# interface_dac_sma_feedback_3PS_LM317_ADC.net
KiCad netlist of a schematic drawn in EAGLE
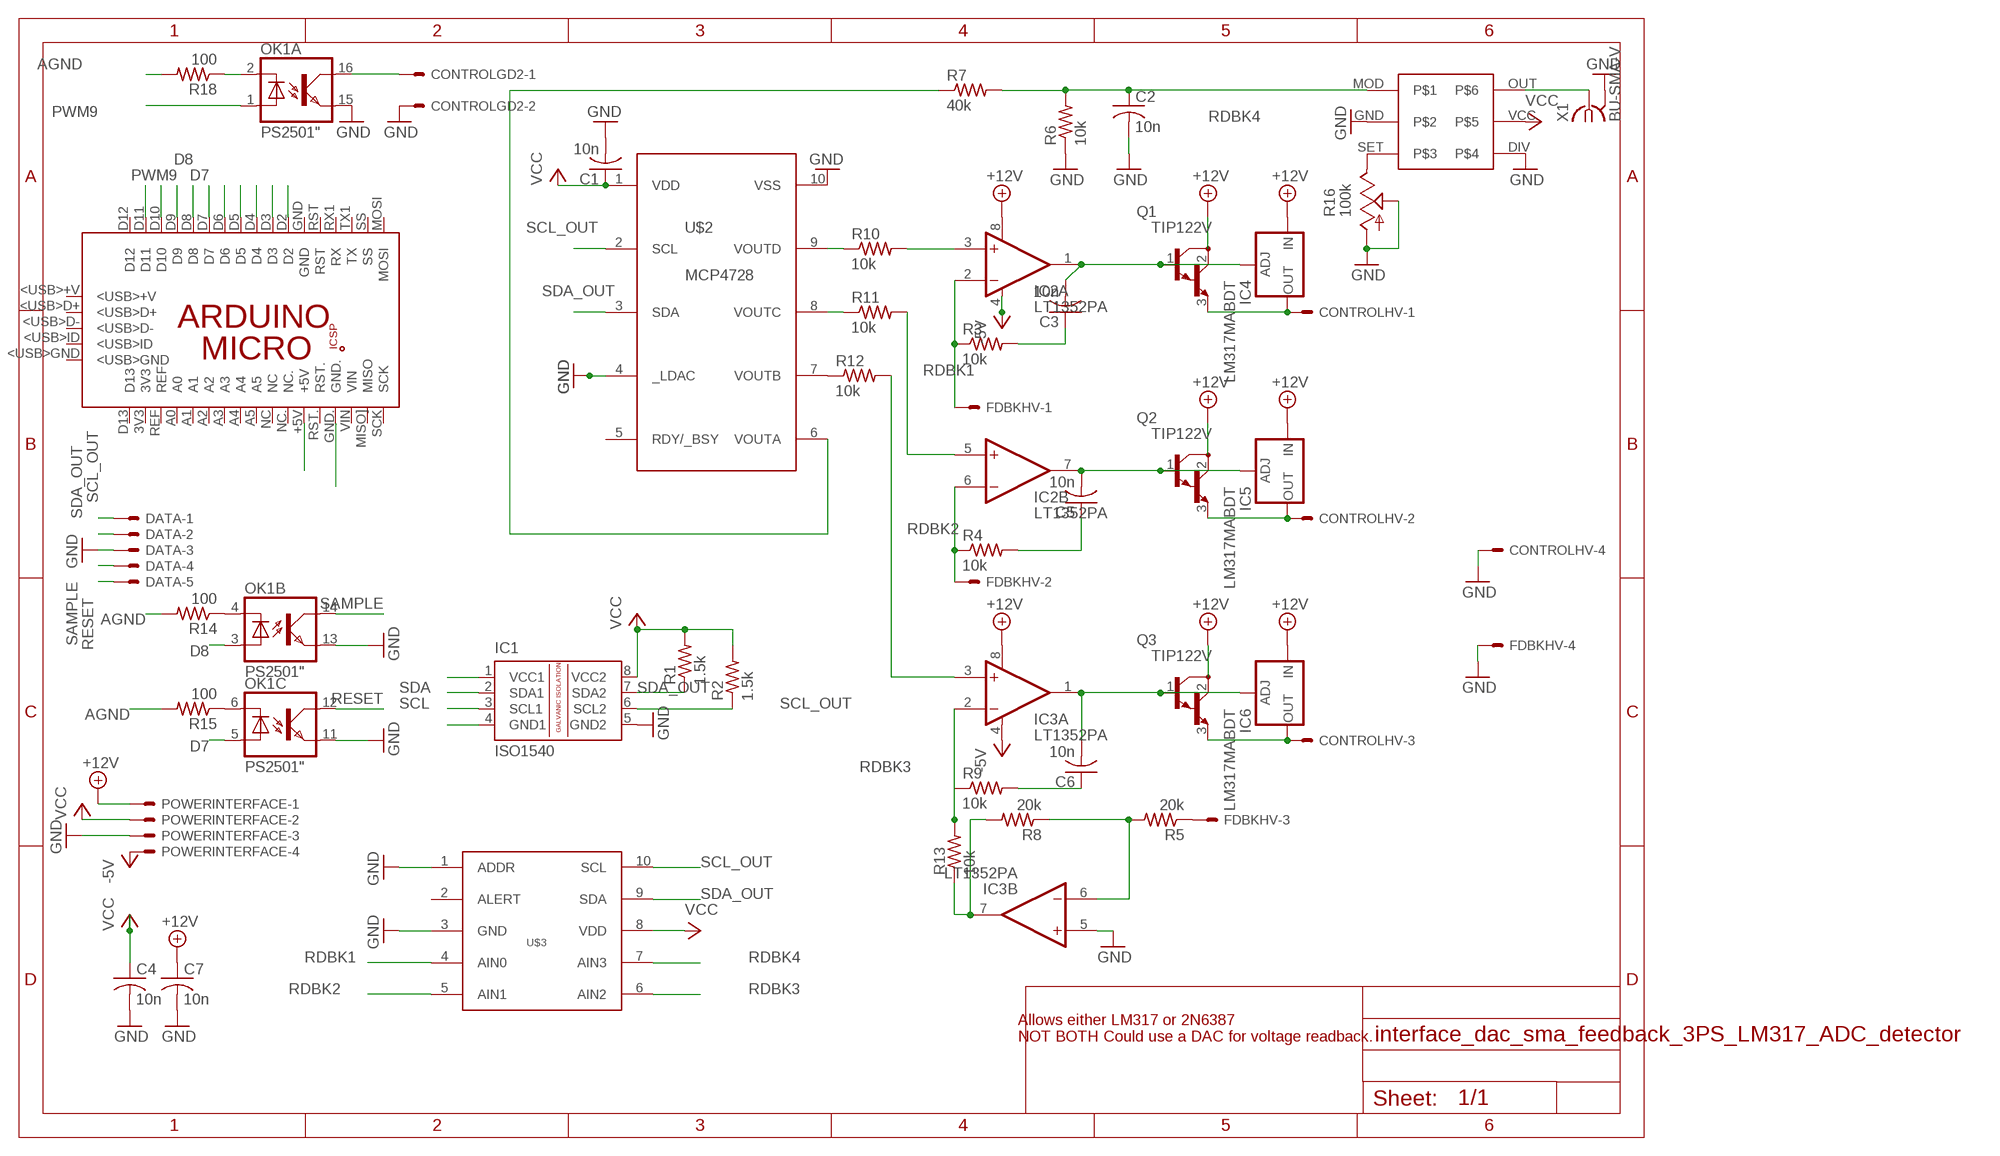
[diagram p0: schematic, sheet 1]

(export (version "E")
  (design (tool "Eeschema 10.0.6"))
  (components
    (comp (ref "C1")
      (value "10n")
      (footprint "eagle-import:C050-024X044")
      (libsource (lib "eagle-import") (part "C-US050-024X044"))
    )
    (comp (ref "C2")
      (value "10n")
      (footprint "eagle-import:C050-024X044")
      (libsource (lib "eagle-import") (part "resistor_C-US050-024X044"))
    )
    (comp (ref "C3")
      (value "10n")
      (footprint "eagle-import:C050-024X044")
      (libsource (lib "eagle-import") (part "resistor_C-US050-024X044"))
    )
    (comp (ref "C4")
      (value "10n")
      (footprint "eagle-import:C050-024X044")
      (libsource (lib "eagle-import") (part "resistor_C-US050-024X044"))
    )
    (comp (ref "C5")
      (value "10n")
      (footprint "eagle-import:C050-024X044")
      (libsource (lib "eagle-import") (part "resistor_C-US050-024X044"))
    )
    (comp (ref "C6")
      (value "10n")
      (footprint "eagle-import:C050-024X044")
      (libsource (lib "eagle-import") (part "resistor_C-US050-024X044"))
    )
    (comp (ref "C7")
      (value "10n")
      (footprint "eagle-import:C050-024X044")
      (libsource (lib "eagle-import") (part "resistor_C-US050-024X044"))
    )
    (comp (ref "CONTROLGD2")
      (value "KK-156-2")
      (footprint "eagle-import:KK-156-2")
      (libsource (lib "eagle-import") (part "KK-156-2"))
    )
    (comp (ref "CONTROLHV")
      (value "KK-156-4")
      (footprint "eagle-import:KK-156-4")
      (libsource (lib "eagle-import") (part "KK-156-4"))
    )
    (comp (ref "DATA")
      (value "KK-156-5")
      (footprint "eagle-import:KK-156-5")
      (libsource (lib "eagle-import") (part "KK-156-5"))
    )
    (comp (ref "FDBKHV")
      (value "KK-156-4")
      (footprint "eagle-import:KK-156-4")
      (libsource (lib "eagle-import") (part "KK-156-4"))
    )
    (comp (ref "IC1")
      (value "ISO1540")
      (footprint "eagle-import:DIL08")
      (libsource (lib "eagle-import") (part "ISO1540"))
    )
    (comp (ref "IC2")
      (value "LT1352PA")
      (footprint "eagle-import:DIL08")
      (libsource (lib "eagle-import") (part "LT1352PA"))
    )
    (comp (ref "IC3")
      (value "LT1352PA")
      (footprint "eagle-import:DIL08")
      (libsource (lib "eagle-import") (part "LT1352PA"))
    )
    (comp (ref "IC4")
      (value "LM317MABDT")
      (footprint "eagle-import:DPACK")
      (libsource (lib "eagle-import") (part "v-reg_LM317?MABDT"))
    )
    (comp (ref "IC5")
      (value "LM317MABDT")
      (footprint "eagle-import:DPACK")
      (libsource (lib "eagle-import") (part "v-reg_LM317?MABDT"))
    )
    (comp (ref "IC6")
      (value "LM317MABDT")
      (footprint "eagle-import:DPACK")
      (libsource (lib "eagle-import") (part "v-reg_LM317?MABDT"))
    )
    (comp (ref "OK1")
      (value "PS2501\"")
      (footprint "eagle-import:DIL16")
      (libsource (lib "eagle-import") (part "PS2501{dblquote}"))
    )
    (comp (ref "PCB1")
      (value "ARDUINO_MICRO")
      (footprint "eagle-import:ARDUINO_MICRO")
      (libsource (lib "eagle-import") (part "ARDUINO_MICRO"))
    )
    (comp (ref "POWERINTERFACE")
      (value "KK-156-4")
      (footprint "eagle-import:KK-156-4")
      (libsource (lib "eagle-import") (part "KK-156-4"))
    )
    (comp (ref "Q1")
      (value "TIP122V")
      (footprint "eagle-import:TO220V")
      (libsource (lib "eagle-import") (part "TIP122V"))
    )
    (comp (ref "Q2")
      (value "TIP122V")
      (footprint "eagle-import:TO220V")
      (libsource (lib "eagle-import") (part "TIP122V"))
    )
    (comp (ref "Q3")
      (value "TIP122V")
      (footprint "eagle-import:TO220V")
      (libsource (lib "eagle-import") (part "TIP122V"))
    )
    (comp (ref "R1")
      (value "1.5k")
      (footprint "eagle-import:0207_12")
      (libsource (lib "eagle-import") (part "resistor_R-US_0207/12"))
    )
    (comp (ref "R2")
      (value "1.5k")
      (footprint "eagle-import:0207_12")
      (libsource (lib "eagle-import") (part "resistor_R-US_0207/12"))
    )
    (comp (ref "R3")
      (value "10k")
      (footprint "eagle-import:0207_12")
      (libsource (lib "eagle-import") (part "resistor_R-US_0207/12"))
    )
    (comp (ref "R4")
      (value "10k")
      (footprint "eagle-import:0207_12")
      (libsource (lib "eagle-import") (part "resistor_R-US_0207/12"))
    )
    (comp (ref "R5")
      (value "20k")
      (footprint "eagle-import:0207_12")
      (libsource (lib "eagle-import") (part "resistor_R-US_0207/12"))
    )
    (comp (ref "R6")
      (value "10k")
      (footprint "eagle-import:0207_12")
      (libsource (lib "eagle-import") (part "resistor_R-US_0207/12"))
    )
    (comp (ref "R7")
      (value "40k")
      (footprint "eagle-import:0207_12")
      (libsource (lib "eagle-import") (part "resistor_R-US_0207/12"))
    )
    (comp (ref "R8")
      (value "20k")
      (footprint "eagle-import:0207_12")
      (libsource (lib "eagle-import") (part "resistor_R-US_0207/12"))
    )
    (comp (ref "R9")
      (value "10k")
      (footprint "eagle-import:0207_12")
      (libsource (lib "eagle-import") (part "resistor_R-US_0207/12"))
    )
    (comp (ref "R10")
      (value "10k")
      (footprint "eagle-import:0207_12")
      (libsource (lib "eagle-import") (part "resistor_R-US_0207/12"))
    )
    (comp (ref "R11")
      (value "10k")
      (footprint "eagle-import:0207_12")
      (libsource (lib "eagle-import") (part "resistor_R-US_0207/12"))
    )
    (comp (ref "R12")
      (value "10k")
      (footprint "eagle-import:0207_12")
      (libsource (lib "eagle-import") (part "resistor_R-US_0207/12"))
    )
    (comp (ref "R13")
      (value "10k")
      (footprint "eagle-import:0207_12")
      (libsource (lib "eagle-import") (part "resistor_R-US_0207/12"))
    )
    (comp (ref "R14")
      (value "100")
      (footprint "eagle-import:0207_12")
      (libsource (lib "eagle-import") (part "R-US_0207/12"))
    )
    (comp (ref "R15")
      (value "100")
      (footprint "eagle-import:0207_12")
      (libsource (lib "eagle-import") (part "R-US_0207/12"))
    )
    (comp (ref "R16")
      (value "100k")
      (footprint "eagle-import:SP19L")
      (libsource (lib "eagle-import") (part "TRIM_US-B90P"))
    )
    (comp (ref "R18")
      (value "100")
      (footprint "eagle-import:0207_12")
      (libsource (lib "eagle-import") (part "R-US_0207/12"))
    )
    (comp (ref "U$1")
      (value "LTC6992")
      (footprint "eagle-import:DIL06")
      (libsource (lib "eagle-import") (part "LTC6992"))
    )
    (comp (ref "U$2")
      (value "MCP4728DIL")
      (footprint "eagle-import:DIL10")
      (libsource (lib "eagle-import") (part "MCP4728DIL"))
    )
    (comp (ref "U$3")
      (value "ADS1015DIL")
      (footprint "eagle-import:DIL10")
      (libsource (lib "eagle-import") (part "ADS1015DIL"))
    )
    (comp (ref "X1")
      (value "BU-SMA-V")
      (footprint "eagle-import:BU-SMA-V")
      (libsource (lib "eagle-import") (part "BU-SMA-V"))
    )
  )
  (nets
    (net (code "1") (name "+12V") (class "Default")
      (node (ref "C7") (pin "1") (pinfunction "1_1") (pintype "passive"))
      (node (ref "IC2") (pin "8") (pinfunction "V+_8") (pintype "power_in"))
      (node (ref "IC3") (pin "8") (pinfunction "V+_8") (pintype "power_in"))
      (node (ref "IC4") (pin "3") (pinfunction "IN_3") (pintype "input"))
      (node (ref "IC5") (pin "3") (pinfunction "IN_3") (pintype "input"))
      (node (ref "IC6") (pin "3") (pinfunction "IN_3") (pintype "input"))
      (node (ref "POWERINTERFACE") (pin "1") (pinfunction "S_1") (pintype "passive"))
      (node (ref "Q1") (pin "2") (pinfunction "C_2") (pintype "passive"))
      (node (ref "Q2") (pin "2") (pinfunction "C_2") (pintype "passive"))
      (node (ref "Q3") (pin "2") (pinfunction "C_2") (pintype "passive"))
    )
    (net (code "2") (name "-5V") (class "Default")
      (node (ref "IC2") (pin "4") (pinfunction "V-_4") (pintype "power_in"))
      (node (ref "IC3") (pin "4") (pinfunction "V-_4") (pintype "power_in"))
      (node (ref "POWERINTERFACE") (pin "4") (pinfunction "S_4") (pintype "passive"))
    )
    (net (code "3") (name "/A+5") (class "Default")
      (node (ref "IC1") (pin "1") (pinfunction "VCC1_1") (pintype "input"))
      (node (ref "PCB1") (pin "+5V") (pinfunction "+5V_+5V") (pintype "bidirectional"))
    )
    (net (code "4") (name "/AGND") (class "Default")
      (node (ref "IC1") (pin "4") (pinfunction "GND1_4") (pintype "input"))
      (node (ref "PCB1") (pin "GND.") (pinfunction "GND._GND.") (pintype "bidirectional"))
      (node (ref "R14") (pin "2") (pinfunction "2_2") (pintype "passive"))
      (node (ref "R15") (pin "2") (pinfunction "2_2") (pintype "passive"))
      (node (ref "R18") (pin "2") (pinfunction "2_2") (pintype "passive"))
    )
    (net (code "5") (name "/D7") (class "Default")
      (node (ref "OK1") (pin "5") (pinfunction "A_5") (pintype "passive"))
      (node (ref "PCB1") (pin "D7") (pinfunction "D7_D7") (pintype "bidirectional"))
    )
    (net (code "6") (name "/D8") (class "Default")
      (node (ref "OK1") (pin "3") (pinfunction "A_3") (pintype "passive"))
      (node (ref "PCB1") (pin "D8") (pinfunction "D8_D8") (pintype "bidirectional"))
    )
    (net (code "7") (name "/PWM9") (class "Default")
      (node (ref "OK1") (pin "1") (pinfunction "A_1") (pintype "passive"))
      (node (ref "PCB1") (pin "D9") (pinfunction "D9_D9") (pintype "bidirectional"))
    )
    (net (code "8") (name "/RDBK1") (class "Default")
      (node (ref "FDBKHV") (pin "1") (pinfunction "S_1") (pintype "passive"))
      (node (ref "IC2") (pin "2") (pinfunction "-IN_2") (pintype "input"))
      (node (ref "R3") (pin "1") (pinfunction "1_1") (pintype "passive"))
      (node (ref "U$3") (pin "4") (pinfunction "AIN0_4") (pintype "bidirectional"))
    )
    (net (code "9") (name "/RDBK2") (class "Default")
      (node (ref "FDBKHV") (pin "2") (pinfunction "S_2") (pintype "passive"))
      (node (ref "IC2") (pin "6") (pinfunction "-IN_6") (pintype "input"))
      (node (ref "R4") (pin "1") (pinfunction "1_1") (pintype "passive"))
      (node (ref "U$3") (pin "5") (pinfunction "AIN1_5") (pintype "bidirectional"))
    )
    (net (code "10") (name "/RDBK3") (class "Default")
      (node (ref "IC3") (pin "2") (pinfunction "-IN_2") (pintype "input"))
      (node (ref "R13") (pin "2") (pinfunction "2_2") (pintype "passive"))
      (node (ref "R9") (pin "1") (pinfunction "1_1") (pintype "passive"))
      (node (ref "U$3") (pin "6") (pinfunction "AIN2_6") (pintype "bidirectional"))
    )
    (net (code "11") (name "/RDBK4") (class "Default")
      (node (ref "C2") (pin "1") (pinfunction "1_1") (pintype "passive"))
      (node (ref "R6") (pin "2") (pinfunction "2_2") (pintype "passive"))
      (node (ref "R7") (pin "2") (pinfunction "2_2") (pintype "passive"))
      (node (ref "U$1") (pin "MOD") (pinfunction "P$1_MOD") (pintype "bidirectional"))
      (node (ref "U$3") (pin "7") (pinfunction "AIN3_7") (pintype "bidirectional"))
    )
    (net (code "12") (name "/RESET") (class "Default")
      (node (ref "DATA") (pin "5") (pinfunction "S_5") (pintype "passive"))
      (node (ref "OK1") (pin "12") (pinfunction "COL_12") (pintype "passive"))
    )
    (net (code "13") (name "/SAMPLE") (class "Default")
      (node (ref "DATA") (pin "4") (pinfunction "S_4") (pintype "passive"))
      (node (ref "OK1") (pin "14") (pinfunction "COL_14") (pintype "passive"))
    )
    (net (code "14") (name "/SCL") (class "Default")
      (node (ref "IC1") (pin "3") (pinfunction "SCL1_3") (pintype "input"))
      (node (ref "PCB1") (pin "D3") (pinfunction "D3_D3") (pintype "bidirectional"))
    )
    (net (code "15") (name "/SCL_OUT") (class "Default")
      (node (ref "DATA") (pin "1") (pinfunction "S_1") (pintype "passive"))
      (node (ref "IC1") (pin "6") (pinfunction "SCL2_6") (pintype "input"))
      (node (ref "R2") (pin "1") (pinfunction "1_1") (pintype "passive"))
      (node (ref "U$2") (pin "2") (pinfunction "SCL_2") (pintype "bidirectional"))
      (node (ref "U$3") (pin "10") (pinfunction "SCL_10") (pintype "bidirectional"))
    )
    (net (code "16") (name "/SDA") (class "Default")
      (node (ref "IC1") (pin "2") (pinfunction "SDA1_2") (pintype "input"))
      (node (ref "PCB1") (pin "D2") (pinfunction "D2_D2") (pintype "bidirectional"))
    )
    (net (code "17") (name "/SDA_OUT") (class "Default")
      (node (ref "DATA") (pin "2") (pinfunction "S_2") (pintype "passive"))
      (node (ref "IC1") (pin "7") (pinfunction "SDA2_7") (pintype "input"))
      (node (ref "R1") (pin "1") (pinfunction "1_1") (pintype "passive"))
      (node (ref "U$2") (pin "3") (pinfunction "SDA_3") (pintype "bidirectional"))
      (node (ref "U$3") (pin "9") (pinfunction "SDA_9") (pintype "bidirectional"))
    )
    (net (code "18") (name "GND") (class "Default")
      (node (ref "C1") (pin "2") (pinfunction "2_2") (pintype "passive"))
      (node (ref "C2") (pin "2") (pinfunction "2_2") (pintype "passive"))
      (node (ref "C4") (pin "2") (pinfunction "2_2") (pintype "passive"))
      (node (ref "C7") (pin "2") (pinfunction "2_2") (pintype "passive"))
      (node (ref "CONTROLGD2") (pin "2") (pinfunction "S_2") (pintype "passive"))
      (node (ref "CONTROLHV") (pin "4") (pinfunction "S_4") (pintype "passive"))
      (node (ref "DATA") (pin "3") (pinfunction "S_3") (pintype "passive"))
      (node (ref "FDBKHV") (pin "4") (pinfunction "S_4") (pintype "passive"))
      (node (ref "IC1") (pin "5") (pinfunction "GND2_5") (pintype "input"))
      (node (ref "IC3") (pin "5") (pinfunction "+IN_5") (pintype "input"))
      (node (ref "OK1") (pin "11") (pinfunction "EMI_11") (pintype "passive"))
      (node (ref "OK1") (pin "13") (pinfunction "EMI_13") (pintype "passive"))
      (node (ref "OK1") (pin "15") (pinfunction "EMI_15") (pintype "passive"))
      (node (ref "POWERINTERFACE") (pin "3") (pinfunction "S_3") (pintype "passive"))
      (node (ref "R16") (pin "A") (pinfunction "A_A") (pintype "passive"))
      (node (ref "R16") (pin "S") (pinfunction "S_S") (pintype "passive"))
      (node (ref "R6") (pin "1") (pinfunction "1_1") (pintype "passive"))
      (node (ref "U$1") (pin "DIV") (pinfunction "P$4_DIV") (pintype "bidirectional"))
      (node (ref "U$1") (pin "GND") (pinfunction "P$2_GND") (pintype "bidirectional"))
      (node (ref "U$2") (pin "10") (pinfunction "VSS_10") (pintype "bidirectional"))
      (node (ref "U$2") (pin "4") (pinfunction "_LDAC_4") (pintype "bidirectional"))
      (node (ref "U$3") (pin "1") (pinfunction "ADDR_1") (pintype "bidirectional"))
      (node (ref "U$3") (pin "3") (pinfunction "GND_3") (pintype "bidirectional"))
      (node (ref "X1") (pin "2") (pinfunction "2_2") (pintype "passive"))
      (node (ref "X1") (pin "3") (pinfunction "2_3") (pintype "passive"))
      (node (ref "X1") (pin "4") (pinfunction "2_4") (pintype "passive"))
      (node (ref "X1") (pin "5") (pinfunction "2_5") (pintype "passive"))
    )
    (net (code "19") (name "Net-(C3-Pad1)") (class "Default")
      (node (ref "C3") (pin "1") (pinfunction "1_1") (pintype "passive"))
      (node (ref "R3") (pin "2") (pinfunction "2_2") (pintype "passive"))
    )
    (net (code "20") (name "Net-(C5-Pad1)") (class "Default")
      (node (ref "C5") (pin "1") (pinfunction "1_1") (pintype "passive"))
      (node (ref "R4") (pin "2") (pinfunction "2_2") (pintype "passive"))
    )
    (net (code "21") (name "Net-(C6-Pad1)") (class "Default")
      (node (ref "C6") (pin "1") (pinfunction "1_1") (pintype "passive"))
      (node (ref "R9") (pin "2") (pinfunction "2_2") (pintype "passive"))
    )
    (net (code "22") (name "Net-(CONTROLGD2A-S)") (class "Default")
      (node (ref "CONTROLGD2") (pin "1") (pinfunction "S_1") (pintype "passive"))
      (node (ref "OK1") (pin "16") (pinfunction "COL_16") (pintype "passive"))
    )
    (net (code "23") (name "Net-(CONTROLHVA-S)") (class "Default")
      (node (ref "CONTROLHV") (pin "1") (pinfunction "S_1") (pintype "passive"))
      (node (ref "IC4") (pin "4") (pinfunction "OUT_4") (pintype "passive"))
      (node (ref "Q1") (pin "3") (pinfunction "E_3") (pintype "passive"))
    )
    (net (code "24") (name "Net-(CONTROLHVB-S)") (class "Default")
      (node (ref "CONTROLHV") (pin "2") (pinfunction "S_2") (pintype "passive"))
      (node (ref "IC5") (pin "4") (pinfunction "OUT_4") (pintype "passive"))
      (node (ref "Q2") (pin "3") (pinfunction "E_3") (pintype "passive"))
    )
    (net (code "25") (name "Net-(CONTROLHVC-S)") (class "Default")
      (node (ref "CONTROLHV") (pin "3") (pinfunction "S_3") (pintype "passive"))
      (node (ref "IC6") (pin "4") (pinfunction "OUT_4") (pintype "passive"))
      (node (ref "Q3") (pin "3") (pinfunction "E_3") (pintype "passive"))
    )
    (net (code "26") (name "Net-(FDBKHVC-S)") (class "Default")
      (node (ref "FDBKHV") (pin "3") (pinfunction "S_3") (pintype "passive"))
      (node (ref "R5") (pin "1") (pinfunction "1_1") (pintype "passive"))
    )
    (net (code "27") (name "Net-(IC2A-+IN)") (class "Default")
      (node (ref "IC2") (pin "3") (pinfunction "+IN_3") (pintype "input"))
      (node (ref "R10") (pin "2") (pinfunction "2_2") (pintype "passive"))
    )
    (net (code "28") (name "Net-(IC2A-OUT)") (class "Default")
      (node (ref "C3") (pin "2") (pinfunction "2_2") (pintype "passive"))
      (node (ref "IC2") (pin "1") (pinfunction "OUT_1") (pintype "output"))
      (node (ref "IC4") (pin "1") (pinfunction "ADJ_1") (pintype "input"))
      (node (ref "Q1") (pin "1") (pinfunction "B_1") (pintype "passive"))
    )
    (net (code "29") (name "Net-(IC2B-+IN)") (class "Default")
      (node (ref "IC2") (pin "5") (pinfunction "+IN_5") (pintype "input"))
      (node (ref "R11") (pin "2") (pinfunction "2_2") (pintype "passive"))
    )
    (net (code "30") (name "Net-(IC2B-OUT)") (class "Default")
      (node (ref "C5") (pin "2") (pinfunction "2_2") (pintype "passive"))
      (node (ref "IC2") (pin "7") (pinfunction "OUT_7") (pintype "output"))
      (node (ref "IC5") (pin "1") (pinfunction "ADJ_1") (pintype "input"))
      (node (ref "Q2") (pin "1") (pinfunction "B_1") (pintype "passive"))
    )
    (net (code "31") (name "Net-(IC3A-+IN)") (class "Default")
      (node (ref "IC3") (pin "3") (pinfunction "+IN_3") (pintype "input"))
      (node (ref "R12") (pin "2") (pinfunction "2_2") (pintype "passive"))
    )
    (net (code "32") (name "Net-(IC3A-OUT)") (class "Default")
      (node (ref "C6") (pin "2") (pinfunction "2_2") (pintype "passive"))
      (node (ref "IC3") (pin "1") (pinfunction "OUT_1") (pintype "output"))
      (node (ref "IC6") (pin "1") (pinfunction "ADJ_1") (pintype "input"))
      (node (ref "Q3") (pin "1") (pinfunction "B_1") (pintype "passive"))
    )
    (net (code "33") (name "Net-(IC3B--IN)") (class "Default")
      (node (ref "IC3") (pin "6") (pinfunction "-IN_6") (pintype "input"))
      (node (ref "R5") (pin "2") (pinfunction "2_2") (pintype "passive"))
      (node (ref "R8") (pin "1") (pinfunction "1_1") (pintype "passive"))
    )
    (net (code "34") (name "Net-(IC3B-OUT)") (class "Default")
      (node (ref "IC3") (pin "7") (pinfunction "OUT_7") (pintype "output"))
      (node (ref "R13") (pin "1") (pinfunction "1_1") (pintype "passive"))
      (node (ref "R8") (pin "2") (pinfunction "2_2") (pintype "passive"))
    )
    (net (code "35") (name "Net-(OK1A-C)") (class "Default")
      (node (ref "OK1") (pin "2") (pinfunction "C_2") (pintype "passive"))
      (node (ref "R18") (pin "1") (pinfunction "1_1") (pintype "passive"))
    )
    (net (code "36") (name "Net-(OK1B-C)") (class "Default")
      (node (ref "OK1") (pin "4") (pinfunction "C_4") (pintype "passive"))
      (node (ref "R14") (pin "1") (pinfunction "1_1") (pintype "passive"))
    )
    (net (code "37") (name "Net-(OK1C-C)") (class "Default")
      (node (ref "OK1") (pin "6") (pinfunction "C_6") (pintype "passive"))
      (node (ref "R15") (pin "1") (pinfunction "1_1") (pintype "passive"))
    )
    (net (code "38") (name "Net-(U$1-P$3)") (class "Default")
      (node (ref "R16") (pin "E") (pinfunction "E_E") (pintype "passive"))
      (node (ref "U$1") (pin "SET") (pinfunction "P$3_SET") (pintype "bidirectional"))
    )
    (net (code "39") (name "Net-(U$1-P$6)") (class "Default")
      (node (ref "U$1") (pin "OUT") (pinfunction "P$6_OUT") (pintype "bidirectional"))
      (node (ref "X1") (pin "1") (pinfunction "1_1") (pintype "passive"))
    )
    (net (code "40") (name "Net-(U$2-VOUTA)") (class "Default")
      (node (ref "R7") (pin "1") (pinfunction "1_1") (pintype "passive"))
      (node (ref "U$2") (pin "6") (pinfunction "VOUTA_6") (pintype "bidirectional"))
    )
    (net (code "41") (name "Net-(U$2-VOUTB)") (class "Default")
      (node (ref "R12") (pin "1") (pinfunction "1_1") (pintype "passive"))
      (node (ref "U$2") (pin "7") (pinfunction "VOUTB_7") (pintype "bidirectional"))
    )
    (net (code "42") (name "Net-(U$2-VOUTC)") (class "Default")
      (node (ref "R11") (pin "1") (pinfunction "1_1") (pintype "passive"))
      (node (ref "U$2") (pin "8") (pinfunction "VOUTC_8") (pintype "bidirectional"))
    )
    (net (code "43") (name "Net-(U$2-VOUTD)") (class "Default")
      (node (ref "R10") (pin "1") (pinfunction "1_1") (pintype "passive"))
      (node (ref "U$2") (pin "9") (pinfunction "VOUTD_9") (pintype "bidirectional"))
    )
    (net (code "44") (name "VCC") (class "Default")
      (node (ref "C1") (pin "1") (pinfunction "1_1") (pintype "passive"))
      (node (ref "C4") (pin "1") (pinfunction "1_1") (pintype "passive"))
      (node (ref "IC1") (pin "8") (pinfunction "VCC2_8") (pintype "input"))
      (node (ref "POWERINTERFACE") (pin "2") (pinfunction "S_2") (pintype "passive"))
      (node (ref "R1") (pin "2") (pinfunction "2_2") (pintype "passive"))
      (node (ref "R2") (pin "2") (pinfunction "2_2") (pintype "passive"))
      (node (ref "U$1") (pin "VCC") (pinfunction "P$5_VCC") (pintype "bidirectional"))
      (node (ref "U$2") (pin "1") (pinfunction "VDD_1") (pintype "bidirectional"))
      (node (ref "U$3") (pin "8") (pinfunction "VDD_8") (pintype "bidirectional"))
    )
    (net (code "45") (name "unconnected-(PCB1-MISO-PadMISO])") (class "Default")
      (node (ref "PCB1") (pin "MISO]") (pinfunction "MISO_MISO]") (pintype "bidirectional"))
    )
    (net (code "46") (name "unconnected-(PCB1-Pad3V3)") (class "Default")
      (node (ref "PCB1") (pin "3V3") (pinfunction "3V3_3V3") (pintype "bidirectional"))
    )
    (net (code "47") (name "unconnected-(PCB1-Pad5V)") (class "Default")
      (node (ref "PCB1") (pin "5V") (pinfunction "5V_5V") (pintype "bidirectional"))
    )
    (net (code "48") (name "unconnected-(PCB1-Pad<USB>+V)") (class "Default")
      (node (ref "PCB1") (pin "<USB>+V") (pinfunction "<USB>+V_<USB>+V") (pintype "bidirectional"))
    )
    (net (code "49") (name "unconnected-(PCB1-Pad<USB>D+)") (class "Default")
      (node (ref "PCB1") (pin "<USB>D+") (pinfunction "<USB>D+_<USB>D+") (pintype "bidirectional"))
    )
    (net (code "50") (name "unconnected-(PCB1-Pad<USB>D-)") (class "Default")
      (node (ref "PCB1") (pin "<USB>D-") (pinfunction "<USB>D-_<USB>D-") (pintype "bidirectional"))
    )
    (net (code "51") (name "unconnected-(PCB1-Pad<USB>GND)") (class "Default")
      (node (ref "PCB1") (pin "<USB>GND") (pinfunction "<USB>GND_<USB>GND") (pintype "bidirectional"))
    )
    (net (code "52") (name "unconnected-(PCB1-Pad<USB>ID)") (class "Default")
      (node (ref "PCB1") (pin "<USB>ID") (pinfunction "<USB>ID_<USB>ID") (pintype "bidirectional"))
    )
    (net (code "53") (name "unconnected-(PCB1-PadA0)") (class "Default")
      (node (ref "PCB1") (pin "A0") (pinfunction "A0_A0") (pintype "bidirectional"))
    )
    (net (code "54") (name "unconnected-(PCB1-PadA1)") (class "Default")
      (node (ref "PCB1") (pin "A1") (pinfunction "A1_A1") (pintype "bidirectional"))
    )
    (net (code "55") (name "unconnected-(PCB1-PadA2)") (class "Default")
      (node (ref "PCB1") (pin "A2") (pinfunction "A2_A2") (pintype "bidirectional"))
    )
    (net (code "56") (name "unconnected-(PCB1-PadA3)") (class "Default")
      (node (ref "PCB1") (pin "A3") (pinfunction "A3_A3") (pintype "bidirectional"))
    )
    (net (code "57") (name "unconnected-(PCB1-PadA4)") (class "Default")
      (node (ref "PCB1") (pin "A4") (pinfunction "A4_A4") (pintype "bidirectional"))
    )
    (net (code "58") (name "unconnected-(PCB1-PadA5)") (class "Default")
      (node (ref "PCB1") (pin "A5") (pinfunction "A5_A5") (pintype "bidirectional"))
    )
    (net (code "59") (name "unconnected-(PCB1-PadD4)") (class "Default")
      (node (ref "PCB1") (pin "D4") (pinfunction "D4_D4") (pintype "bidirectional"))
    )
    (net (code "60") (name "unconnected-(PCB1-PadD5)") (class "Default")
      (node (ref "PCB1") (pin "D5") (pinfunction "D5_D5") (pintype "bidirectional"))
    )
    (net (code "61") (name "unconnected-(PCB1-PadD6)") (class "Default")
      (node (ref "PCB1") (pin "D6") (pinfunction "D6_D6") (pintype "bidirectional"))
    )
    (net (code "62") (name "unconnected-(PCB1-PadD10)") (class "Default")
      (node (ref "PCB1") (pin "D10") (pinfunction "D10_D10") (pintype "bidirectional"))
    )
    (net (code "63") (name "unconnected-(PCB1-PadD11)") (class "Default")
      (node (ref "PCB1") (pin "D11") (pinfunction "D11_D11") (pintype "bidirectional"))
    )
    (net (code "64") (name "unconnected-(PCB1-PadD12)") (class "Default")
      (node (ref "PCB1") (pin "D12") (pinfunction "D12_D12") (pintype "bidirectional"))
    )
    (net (code "65") (name "unconnected-(PCB1-PadD13)") (class "Default")
      (node (ref "PCB1") (pin "D13") (pinfunction "D13_D13") (pintype "bidirectional"))
    )
    (net (code "66") (name "unconnected-(PCB1-PadGND)") (class "Default")
      (node (ref "PCB1") (pin "GND") (pinfunction "GND_GND") (pintype "bidirectional"))
    )
    (net (code "67") (name "unconnected-(PCB1-PadGND_)") (class "Default")
      (node (ref "PCB1") (pin "GND_") (pinfunction "GND__GND_") (pintype "bidirectional"))
    )
    (net (code "68") (name "unconnected-(PCB1-PadMISO.)") (class "Default")
      (node (ref "PCB1") (pin "MISO.") (pinfunction "MISO._MISO.") (pintype "bidirectional"))
    )
    (net (code "69") (name "unconnected-(PCB1-PadMOSI)") (class "Default")
      (node (ref "PCB1") (pin "MOSI") (pinfunction "MOSI_MOSI") (pintype "bidirectional"))
    )
    (net (code "70") (name "unconnected-(PCB1-PadMOSI.)") (class "Default")
      (node (ref "PCB1") (pin "MOSI.") (pinfunction "MOSI._MOSI.") (pintype "bidirectional"))
    )
    (net (code "71") (name "unconnected-(PCB1-PadNC)") (class "Default")
      (node (ref "PCB1") (pin "NC") (pinfunction "NC_NC") (pintype "bidirectional"))
    )
    (net (code "72") (name "unconnected-(PCB1-PadNC.)") (class "Default")
      (node (ref "PCB1") (pin "NC.") (pinfunction "NC._NC.") (pintype "bidirectional"))
    )
    (net (code "73") (name "unconnected-(PCB1-PadREF)") (class "Default")
      (node (ref "PCB1") (pin "REF") (pinfunction "REF_REF") (pintype "bidirectional"))
    )
    (net (code "74") (name "unconnected-(PCB1-PadRESET..)") (class "Default")
      (node (ref "PCB1") (pin "RESET..") (pinfunction "RESET.._RESET..") (pintype "bidirectional"))
    )
    (net (code "75") (name "unconnected-(PCB1-PadRST)") (class "Default")
      (node (ref "PCB1") (pin "RST") (pinfunction "RST_RST") (pintype "bidirectional"))
    )
    (net (code "76") (name "unconnected-(PCB1-PadRST.)") (class "Default")
      (node (ref "PCB1") (pin "RST.") (pinfunction "RST._RST.") (pintype "bidirectional"))
    )
    (net (code "77") (name "unconnected-(PCB1-PadSCK)") (class "Default")
      (node (ref "PCB1") (pin "SCK") (pinfunction "SCK_SCK") (pintype "bidirectional"))
    )
    (net (code "78") (name "unconnected-(PCB1-PadSCK.)") (class "Default")
      (node (ref "PCB1") (pin "SCK.") (pinfunction "SCK._SCK.") (pintype "bidirectional"))
    )
    (net (code "79") (name "unconnected-(PCB1-PadSS)") (class "Default")
      (node (ref "PCB1") (pin "SS") (pinfunction "SS_SS") (pintype "bidirectional"))
    )
    (net (code "80") (name "unconnected-(PCB1-PadVIN)") (class "Default")
      (node (ref "PCB1") (pin "VIN") (pinfunction "VIN_VIN") (pintype "bidirectional"))
    )
    (net (code "81") (name "unconnected-(PCB1-RX-PadRX1)") (class "Default")
      (node (ref "PCB1") (pin "RX1") (pinfunction "RX_RX1") (pintype "bidirectional"))
    )
    (net (code "82") (name "unconnected-(PCB1-TX-PadTX1)") (class "Default")
      (node (ref "PCB1") (pin "TX1") (pinfunction "TX_TX1") (pintype "bidirectional"))
    )
    (net (code "83") (name "unconnected-(U$2-RDY{slash}_BSY-Pad5)") (class "Default")
      (node (ref "U$2") (pin "5") (pinfunction "RDY/_BSY_5") (pintype "bidirectional"))
    )
    (net (code "84") (name "unconnected-(U$3-ALERT-Pad2)") (class "Default")
      (node (ref "U$3") (pin "2") (pinfunction "ALERT_2") (pintype "bidirectional"))
    )
  )
)
